# Blue_Cobra.net
KiCad netlist of a schematic drawn in EAGLE
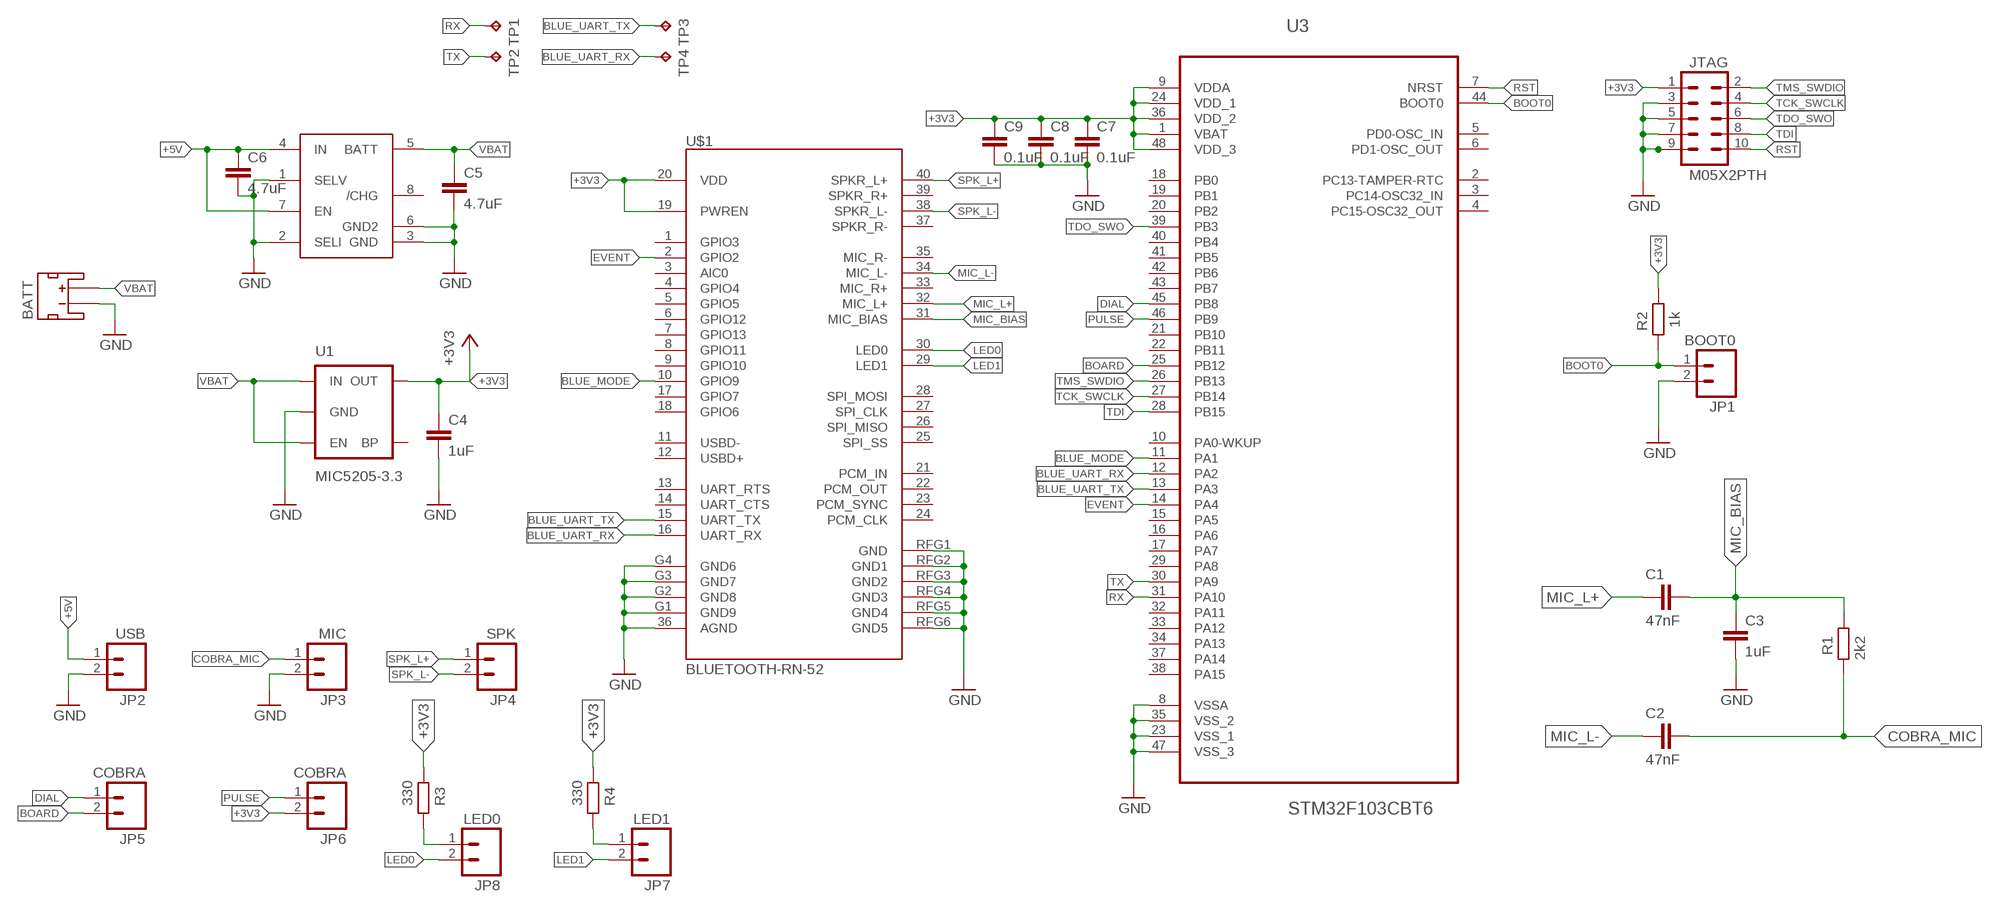
[diagram p0: schematic, sheet 1]

(export (version "E")
  (design (tool "Eeschema 10.0.6"))
  (components
    (comp (ref "BATT")
      (value "JST_2MM_MALE")
      (footprint "eagle-import:JST-2-SMD")
      (libsource (lib "eagle-import") (part "JST_2MM_MALE"))
    )
    (comp (ref "C1")
      (value "47nF")
      (footprint "eagle-import:C0805")
      (libsource (lib "eagle-import") (part "C-EUC0805"))
    )
    (comp (ref "C2")
      (value "47nF")
      (footprint "eagle-import:C0805")
      (libsource (lib "eagle-import") (part "C-EUC0805"))
    )
    (comp (ref "C3")
      (value "1uF")
      (footprint "eagle-import:C0805")
      (libsource (lib "eagle-import") (part "C-EUC0805"))
    )
    (comp (ref "C4")
      (value "1uF")
      (footprint "eagle-import:C0805")
      (libsource (lib "eagle-import") (part "C-EUC0805"))
    )
    (comp (ref "C5")
      (value "4.7uF")
      (footprint "eagle-import:C0805")
      (libsource (lib "eagle-import") (part "C-EUC0805"))
    )
    (comp (ref "C6")
      (value "4.7uF")
      (footprint "eagle-import:C0805")
      (libsource (lib "eagle-import") (part "C-EUC0805"))
    )
    (comp (ref "C7")
      (value "0.1uF")
      (footprint "eagle-import:C0805")
      (libsource (lib "eagle-import") (part "C-EUC0805"))
    )
    (comp (ref "C8")
      (value "0.1uF")
      (footprint "eagle-import:C0805")
      (libsource (lib "eagle-import") (part "C-EUC0805"))
    )
    (comp (ref "C9")
      (value "0.1uF")
      (footprint "eagle-import:C0805")
      (libsource (lib "eagle-import") (part "C-EUC0805"))
    )
    (comp (ref "JP1")
      (value "BOOT0")
      (footprint "eagle-import:1X02_NO_SILK")
      (libsource (lib "eagle-import") (part "M021X02_NO_SILK"))
    )
    (comp (ref "JP2")
      (value "USB")
      (footprint "eagle-import:1X02_NO_SILK")
      (libsource (lib "eagle-import") (part "M021X02_NO_SILK"))
    )
    (comp (ref "JP3")
      (value "MIC")
      (footprint "eagle-import:1X02_NO_SILK")
      (libsource (lib "eagle-import") (part "M021X02_NO_SILK"))
    )
    (comp (ref "JP4")
      (value "SPK")
      (footprint "eagle-import:1X02_NO_SILK")
      (libsource (lib "eagle-import") (part "M021X02_NO_SILK"))
    )
    (comp (ref "JP5")
      (value "COBRA")
      (footprint "eagle-import:1X02_NO_SILK")
      (libsource (lib "eagle-import") (part "M021X02_NO_SILK"))
    )
    (comp (ref "JP6")
      (value "COBRA")
      (footprint "eagle-import:1X02_NO_SILK")
      (libsource (lib "eagle-import") (part "M021X02_NO_SILK"))
    )
    (comp (ref "JP7")
      (value "LED1")
      (footprint "eagle-import:1X02_NO_SILK")
      (libsource (lib "eagle-import") (part "M021X02_NO_SILK"))
    )
    (comp (ref "JP8")
      (value "LED0")
      (footprint "eagle-import:1X02_NO_SILK")
      (libsource (lib "eagle-import") (part "M021X02_NO_SILK"))
    )
    (comp (ref "JTAG")
      (value "M05X2PTH")
      (footprint "eagle-import:AVR_ICSP")
      (libsource (lib "eagle-import") (part "M05X2PTH"))
    )
    (comp (ref "R1")
      (value "2k2")
      (footprint "eagle-import:R0805")
      (libsource (lib "eagle-import") (part "R-EU_R0805"))
    )
    (comp (ref "R2")
      (value "1k")
      (footprint "eagle-import:R0805")
      (libsource (lib "eagle-import") (part "R-EU_R0805"))
    )
    (comp (ref "R3")
      (value "330")
      (footprint "eagle-import:R0805")
      (libsource (lib "eagle-import") (part "R-EU_R0805"))
    )
    (comp (ref "R4")
      (value "330")
      (footprint "eagle-import:R0805")
      (libsource (lib "eagle-import") (part "R-EU_R0805"))
    )
    (comp (ref "TP1")
      (value "TPTP10SQ")
      (footprint "eagle-import:TP10SQ")
      (libsource (lib "eagle-import") (part "TPTP10SQ"))
    )
    (comp (ref "TP2")
      (value "TPTP10SQ")
      (footprint "eagle-import:TP10SQ")
      (libsource (lib "eagle-import") (part "TPTP10SQ"))
    )
    (comp (ref "TP3")
      (value "TPTP10SQ")
      (footprint "eagle-import:TP10SQ")
      (libsource (lib "eagle-import") (part "TPTP10SQ"))
    )
    (comp (ref "TP4")
      (value "TPTP10SQ")
      (footprint "eagle-import:TP10SQ")
      (libsource (lib "eagle-import") (part "TPTP10SQ"))
    )
    (comp (ref "U$1")
      (value "BLUETOOTH-RN-52")
      (footprint "eagle-import:RN-52")
      (libsource (lib "eagle-import") (part "BLUETOOTH-RN-52"))
    )
    (comp (ref "U1")
      (value "MIC5205-3.3")
      (footprint "eagle-import:SOT23-5")
      (libsource (lib "eagle-import") (part "MIC52053.3V"))
    )
    (comp (ref "U2")
      (value "MAX1811SO8")
      (footprint "eagle-import:SO08")
      (libsource (lib "eagle-import") (part "MAX1811SO8"))
    )
    (comp (ref "U3")
      (value "STM32F103CBT6")
      (footprint "eagle-import:QFP50P900X900X160-48N")
      (libsource (lib "eagle-import") (part "STM32F103CBT6"))
    )
  )
  (nets
    (net (code "1") (name "+3V3") (class "Default")
      (node (ref "C4") (pin "1") (pinfunction "1_1") (pintype "passive"))
      (node (ref "C7") (pin "1") (pinfunction "1_1") (pintype "passive"))
      (node (ref "C8") (pin "1") (pinfunction "1_1") (pintype "passive"))
      (node (ref "C9") (pin "1") (pinfunction "1_1") (pintype "passive"))
      (node (ref "JP6") (pin "2") (pinfunction "2_2") (pintype "passive"))
      (node (ref "JTAG") (pin "1") (pinfunction "1_1") (pintype "passive"))
      (node (ref "R2") (pin "2") (pinfunction "2_2") (pintype "passive"))
      (node (ref "R3") (pin "1") (pinfunction "1_1") (pintype "passive"))
      (node (ref "R4") (pin "1") (pinfunction "1_1") (pintype "passive"))
      (node (ref "U$1") (pin "19") (pinfunction "PWREN_19") (pintype "bidirectional"))
      (node (ref "U$1") (pin "20") (pinfunction "VDD_20") (pintype "bidirectional"))
      (node (ref "U1") (pin "5") (pinfunction "OUT_5") (pintype "passive"))
      (node (ref "U3") (pin "1") (pinfunction "VBAT_1") (pintype "input"))
      (node (ref "U3") (pin "24") (pinfunction "VDD_1_24") (pintype "bidirectional"))
      (node (ref "U3") (pin "36") (pinfunction "VDD_2_36") (pintype "power_in"))
      (node (ref "U3") (pin "48") (pinfunction "VDD_3_48") (pintype "power_in"))
      (node (ref "U3") (pin "9") (pinfunction "VDDA_9") (pintype "power_in"))
    )
    (net (code "2") (name "+5V") (class "Default")
      (node (ref "C6") (pin "1") (pinfunction "1_1") (pintype "passive"))
      (node (ref "JP2") (pin "1") (pinfunction "1_1") (pintype "passive"))
      (node (ref "U2") (pin "4") (pinfunction "IN_4") (pintype "bidirectional"))
      (node (ref "U2") (pin "7") (pinfunction "EN_7") (pintype "bidirectional"))
    )
    (net (code "3") (name "/PA11") (class "Default")
      (node (ref "U3") (pin "32") (pinfunction "PA11_32") (pintype "power_in"))
    )
    (net (code "4") (name "BLUE_MODE") (class "Default")
      (node (ref "U$1") (pin "10") (pinfunction "GPIO9_10") (pintype "bidirectional"))
      (node (ref "U3") (pin "11") (pinfunction "PA1_11") (pintype "bidirectional"))
    )
    (net (code "5") (name "BLUE_UART_RX") (class "Default")
      (node (ref "TP4") (pin "TP") (pinfunction "TP_TP") (pintype "input"))
      (node (ref "U$1") (pin "16") (pinfunction "UART_RX_16") (pintype "bidirectional"))
      (node (ref "U3") (pin "12") (pinfunction "PA2_12") (pintype "bidirectional"))
    )
    (net (code "6") (name "BLUE_UART_TX") (class "Default")
      (node (ref "TP3") (pin "TP") (pinfunction "TP_TP") (pintype "input"))
      (node (ref "U$1") (pin "15") (pinfunction "UART_TX_15") (pintype "bidirectional"))
      (node (ref "U3") (pin "13") (pinfunction "PA3_13") (pintype "bidirectional"))
    )
    (net (code "7") (name "BOARD") (class "Default")
      (node (ref "JP5") (pin "2") (pinfunction "2_2") (pintype "passive"))
      (node (ref "U3") (pin "25") (pinfunction "PB12_25") (pintype "bidirectional"))
    )
    (net (code "8") (name "BOOT0") (class "Default")
      (node (ref "JP1") (pin "1") (pinfunction "1_1") (pintype "passive"))
      (node (ref "R2") (pin "1") (pinfunction "1_1") (pintype "passive"))
      (node (ref "U3") (pin "44") (pinfunction "BOOT0_44") (pintype "bidirectional"))
    )
    (net (code "9") (name "COBRA_MIC") (class "Default")
      (node (ref "C2") (pin "2") (pinfunction "2_2") (pintype "passive"))
      (node (ref "JP3") (pin "1") (pinfunction "1_1") (pintype "passive"))
      (node (ref "R1") (pin "1") (pinfunction "1_1") (pintype "passive"))
    )
    (net (code "10") (name "DIAL") (class "Default")
      (node (ref "JP5") (pin "1") (pinfunction "1_1") (pintype "passive"))
      (node (ref "U3") (pin "45") (pinfunction "PB8_45") (pintype "bidirectional"))
    )
    (net (code "11") (name "EVENT") (class "Default")
      (node (ref "U$1") (pin "2") (pinfunction "GPIO2_2") (pintype "bidirectional"))
      (node (ref "U3") (pin "14") (pinfunction "PA4_14") (pintype "bidirectional"))
    )
    (net (code "12") (name "GND") (class "Default")
      (node (ref "BATT") (pin "1") (pinfunction "-_1") (pintype "bidirectional"))
      (node (ref "C3") (pin "2") (pinfunction "2_2") (pintype "passive"))
      (node (ref "C4") (pin "2") (pinfunction "2_2") (pintype "passive"))
      (node (ref "C5") (pin "2") (pinfunction "2_2") (pintype "passive"))
      (node (ref "C6") (pin "2") (pinfunction "2_2") (pintype "passive"))
      (node (ref "C7") (pin "2") (pinfunction "2_2") (pintype "passive"))
      (node (ref "C8") (pin "2") (pinfunction "2_2") (pintype "passive"))
      (node (ref "C9") (pin "2") (pinfunction "2_2") (pintype "passive"))
      (node (ref "JP1") (pin "2") (pinfunction "2_2") (pintype "passive"))
      (node (ref "JP2") (pin "2") (pinfunction "2_2") (pintype "passive"))
      (node (ref "JP3") (pin "2") (pinfunction "2_2") (pintype "passive"))
      (node (ref "JTAG") (pin "3") (pinfunction "3_3") (pintype "passive"))
      (node (ref "JTAG") (pin "5") (pinfunction "5_5") (pintype "passive"))
      (node (ref "JTAG") (pin "7") (pinfunction "7_7") (pintype "passive"))
      (node (ref "JTAG") (pin "9") (pinfunction "9_9") (pintype "passive"))
      (node (ref "U$1") (pin "36") (pinfunction "AGND_36") (pintype "bidirectional"))
      (node (ref "U$1") (pin "G1") (pinfunction "GND9_G1") (pintype "bidirectional"))
      (node (ref "U$1") (pin "G2") (pinfunction "GND8_G2") (pintype "bidirectional"))
      (node (ref "U$1") (pin "G3") (pinfunction "GND7_G3") (pintype "bidirectional"))
      (node (ref "U$1") (pin "G4") (pinfunction "GND6_G4") (pintype "bidirectional"))
      (node (ref "U$1") (pin "RFG1") (pinfunction "GND_RFG1") (pintype "bidirectional"))
      (node (ref "U$1") (pin "RFG2") (pinfunction "GND1_RFG2") (pintype "bidirectional"))
      (node (ref "U$1") (pin "RFG3") (pinfunction "GND2_RFG3") (pintype "bidirectional"))
      (node (ref "U$1") (pin "RFG4") (pinfunction "GND3_RFG4") (pintype "bidirectional"))
      (node (ref "U$1") (pin "RFG5") (pinfunction "GND4_RFG5") (pintype "bidirectional"))
      (node (ref "U$1") (pin "RFG6") (pinfunction "GND5_RFG6") (pintype "bidirectional"))
      (node (ref "U1") (pin "2") (pinfunction "GND_2") (pintype "input"))
      (node (ref "U2") (pin "1") (pinfunction "SELV_1") (pintype "bidirectional"))
      (node (ref "U2") (pin "2") (pinfunction "SELI_2") (pintype "bidirectional"))
      (node (ref "U2") (pin "3") (pinfunction "GND_3") (pintype "bidirectional"))
      (node (ref "U2") (pin "6") (pinfunction "GND2_6") (pintype "bidirectional"))
      (node (ref "U3") (pin "23") (pinfunction "VSS_1_23") (pintype "bidirectional"))
      (node (ref "U3") (pin "35") (pinfunction "VSS_2_35") (pintype "passive"))
      (node (ref "U3") (pin "47") (pinfunction "VSS_3_47") (pintype "passive"))
      (node (ref "U3") (pin "8") (pinfunction "VSSA_8") (pintype "passive"))
    )
    (net (code "13") (name "LED0") (class "Default")
      (node (ref "JP8") (pin "2") (pinfunction "2_2") (pintype "passive"))
      (node (ref "U$1") (pin "30") (pinfunction "LED0_30") (pintype "bidirectional"))
    )
    (net (code "14") (name "LED1") (class "Default")
      (node (ref "JP7") (pin "2") (pinfunction "2_2") (pintype "passive"))
      (node (ref "U$1") (pin "29") (pinfunction "LED1_29") (pintype "bidirectional"))
    )
    (net (code "15") (name "MIC_BIAS") (class "Default")
      (node (ref "C1") (pin "2") (pinfunction "2_2") (pintype "passive"))
      (node (ref "C3") (pin "1") (pinfunction "1_1") (pintype "passive"))
      (node (ref "R1") (pin "2") (pinfunction "2_2") (pintype "passive"))
      (node (ref "U$1") (pin "31") (pinfunction "MIC_BIAS_31") (pintype "bidirectional"))
    )
    (net (code "16") (name "MIC_L+") (class "Default")
      (node (ref "C1") (pin "1") (pinfunction "1_1") (pintype "passive"))
      (node (ref "U$1") (pin "32") (pinfunction "MIC_L+_32") (pintype "bidirectional"))
    )
    (net (code "17") (name "MIC_L-") (class "Default")
      (node (ref "C2") (pin "1") (pinfunction "1_1") (pintype "passive"))
      (node (ref "U$1") (pin "34") (pinfunction "MIC_L-_34") (pintype "bidirectional"))
    )
    (net (code "18") (name "Net-(JP7-Pad1)") (class "Default")
      (node (ref "JP7") (pin "1") (pinfunction "1_1") (pintype "passive"))
      (node (ref "R4") (pin "2") (pinfunction "2_2") (pintype "passive"))
    )
    (net (code "19") (name "Net-(JP8-Pad1)") (class "Default")
      (node (ref "JP8") (pin "1") (pinfunction "1_1") (pintype "passive"))
      (node (ref "R3") (pin "2") (pinfunction "2_2") (pintype "passive"))
    )
    (net (code "20") (name "PULSE") (class "Default")
      (node (ref "JP6") (pin "1") (pinfunction "1_1") (pintype "passive"))
      (node (ref "U3") (pin "46") (pinfunction "PB9_46") (pintype "bidirectional"))
    )
    (net (code "21") (name "RST") (class "Default")
      (node (ref "JTAG") (pin "10") (pinfunction "10_10") (pintype "passive"))
      (node (ref "U3") (pin "7") (pinfunction "NRST_7") (pintype "bidirectional"))
    )
    (net (code "22") (name "RX") (class "Default")
      (node (ref "TP1") (pin "TP") (pinfunction "TP_TP") (pintype "input"))
      (node (ref "U3") (pin "31") (pinfunction "PA10_31") (pintype "bidirectional"))
    )
    (net (code "23") (name "SPK_L+") (class "Default")
      (node (ref "JP4") (pin "1") (pinfunction "1_1") (pintype "passive"))
      (node (ref "U$1") (pin "40") (pinfunction "SPKR_L+_40") (pintype "bidirectional"))
    )
    (net (code "24") (name "SPK_L-") (class "Default")
      (node (ref "JP4") (pin "2") (pinfunction "2_2") (pintype "passive"))
      (node (ref "U$1") (pin "38") (pinfunction "SPKR_L-_38") (pintype "bidirectional"))
    )
    (net (code "25") (name "TCK_SWCLK") (class "Default")
      (node (ref "JTAG") (pin "4") (pinfunction "4_4") (pintype "passive"))
      (node (ref "U3") (pin "27") (pinfunction "PB14_27") (pintype "bidirectional"))
    )
    (net (code "26") (name "TDI") (class "Default")
      (node (ref "JTAG") (pin "8") (pinfunction "8_8") (pintype "passive"))
      (node (ref "U3") (pin "28") (pinfunction "PB15_28") (pintype "bidirectional"))
    )
    (net (code "27") (name "TDO_SWO") (class "Default")
      (node (ref "JTAG") (pin "6") (pinfunction "6_6") (pintype "passive"))
      (node (ref "U3") (pin "39") (pinfunction "PB3_39") (pintype "bidirectional"))
    )
    (net (code "28") (name "TMS_SWDIO") (class "Default")
      (node (ref "JTAG") (pin "2") (pinfunction "2_2") (pintype "passive"))
      (node (ref "U3") (pin "26") (pinfunction "PB13_26") (pintype "bidirectional"))
    )
    (net (code "29") (name "TX") (class "Default")
      (node (ref "TP2") (pin "TP") (pinfunction "TP_TP") (pintype "input"))
      (node (ref "U3") (pin "30") (pinfunction "PA9_30") (pintype "bidirectional"))
    )
    (net (code "30") (name "VBAT") (class "Default")
      (node (ref "BATT") (pin "2") (pinfunction "+_2") (pintype "bidirectional"))
      (node (ref "C5") (pin "1") (pinfunction "1_1") (pintype "passive"))
      (node (ref "U1") (pin "1") (pinfunction "IN_1") (pintype "input"))
      (node (ref "U1") (pin "3") (pinfunction "EN_3") (pintype "input"))
      (node (ref "U2") (pin "5") (pinfunction "BATT_5") (pintype "bidirectional"))
    )
    (net (code "31") (name "unconnected-(BATT-PAD1-PadNC1)") (class "Default")
      (node (ref "BATT") (pin "NC1") (pinfunction "PAD1_NC1") (pintype "bidirectional"))
    )
    (net (code "32") (name "unconnected-(BATT-PAD2-PadNC2)") (class "Default")
      (node (ref "BATT") (pin "NC2") (pinfunction "PAD2_NC2") (pintype "bidirectional"))
    )
    (net (code "33") (name "unconnected-(U$1-AIC0-Pad3)") (class "Default")
      (node (ref "U$1") (pin "3") (pinfunction "AIC0_3") (pintype "bidirectional"))
    )
    (net (code "34") (name "unconnected-(U$1-GPIO3-Pad1)") (class "Default")
      (node (ref "U$1") (pin "1") (pinfunction "GPIO3_1") (pintype "bidirectional"))
    )
    (net (code "35") (name "unconnected-(U$1-GPIO4-Pad4)") (class "Default")
      (node (ref "U$1") (pin "4") (pinfunction "GPIO4_4") (pintype "bidirectional"))
    )
    (net (code "36") (name "unconnected-(U$1-GPIO5-Pad5)") (class "Default")
      (node (ref "U$1") (pin "5") (pinfunction "GPIO5_5") (pintype "bidirectional"))
    )
    (net (code "37") (name "unconnected-(U$1-GPIO6-Pad18)") (class "Default")
      (node (ref "U$1") (pin "18") (pinfunction "GPIO6_18") (pintype "bidirectional"))
    )
    (net (code "38") (name "unconnected-(U$1-GPIO7-Pad17)") (class "Default")
      (node (ref "U$1") (pin "17") (pinfunction "GPIO7_17") (pintype "bidirectional"))
    )
    (net (code "39") (name "unconnected-(U$1-GPIO10-Pad9)") (class "Default")
      (node (ref "U$1") (pin "9") (pinfunction "GPIO10_9") (pintype "bidirectional"))
    )
    (net (code "40") (name "unconnected-(U$1-GPIO11-Pad8)") (class "Default")
      (node (ref "U$1") (pin "8") (pinfunction "GPIO11_8") (pintype "bidirectional"))
    )
    (net (code "41") (name "unconnected-(U$1-GPIO12-Pad6)") (class "Default")
      (node (ref "U$1") (pin "6") (pinfunction "GPIO12_6") (pintype "bidirectional"))
    )
    (net (code "42") (name "unconnected-(U$1-GPIO13-Pad7)") (class "Default")
      (node (ref "U$1") (pin "7") (pinfunction "GPIO13_7") (pintype "bidirectional"))
    )
    (net (code "43") (name "unconnected-(U$1-MIC_R+-Pad33)") (class "Default")
      (node (ref "U$1") (pin "33") (pinfunction "MIC_R+_33") (pintype "bidirectional"))
    )
    (net (code "44") (name "unconnected-(U$1-MIC_R--Pad35)") (class "Default")
      (node (ref "U$1") (pin "35") (pinfunction "MIC_R-_35") (pintype "bidirectional"))
    )
    (net (code "45") (name "unconnected-(U$1-PCM_CLK-Pad24)") (class "Default")
      (node (ref "U$1") (pin "24") (pinfunction "PCM_CLK_24") (pintype "bidirectional"))
    )
    (net (code "46") (name "unconnected-(U$1-PCM_IN-Pad21)") (class "Default")
      (node (ref "U$1") (pin "21") (pinfunction "PCM_IN_21") (pintype "bidirectional"))
    )
    (net (code "47") (name "unconnected-(U$1-PCM_OUT-Pad22)") (class "Default")
      (node (ref "U$1") (pin "22") (pinfunction "PCM_OUT_22") (pintype "bidirectional"))
    )
    (net (code "48") (name "unconnected-(U$1-PCM_SYNC-Pad23)") (class "Default")
      (node (ref "U$1") (pin "23") (pinfunction "PCM_SYNC_23") (pintype "bidirectional"))
    )
    (net (code "49") (name "unconnected-(U$1-SPI_CLK-Pad27)") (class "Default")
      (node (ref "U$1") (pin "27") (pinfunction "SPI_CLK_27") (pintype "bidirectional"))
    )
    (net (code "50") (name "unconnected-(U$1-SPI_MISO-Pad26)") (class "Default")
      (node (ref "U$1") (pin "26") (pinfunction "SPI_MISO_26") (pintype "bidirectional"))
    )
    (net (code "51") (name "unconnected-(U$1-SPI_MOSI-Pad28)") (class "Default")
      (node (ref "U$1") (pin "28") (pinfunction "SPI_MOSI_28") (pintype "bidirectional"))
    )
    (net (code "52") (name "unconnected-(U$1-SPI_SS-Pad25)") (class "Default")
      (node (ref "U$1") (pin "25") (pinfunction "SPI_SS_25") (pintype "bidirectional"))
    )
    (net (code "53") (name "unconnected-(U$1-SPKR_R+-Pad39)") (class "Default")
      (node (ref "U$1") (pin "39") (pinfunction "SPKR_R+_39") (pintype "bidirectional"))
    )
    (net (code "54") (name "unconnected-(U$1-SPKR_R--Pad37)") (class "Default")
      (node (ref "U$1") (pin "37") (pinfunction "SPKR_R-_37") (pintype "bidirectional"))
    )
    (net (code "55") (name "unconnected-(U$1-UART_CTS-Pad14)") (class "Default")
      (node (ref "U$1") (pin "14") (pinfunction "UART_CTS_14") (pintype "bidirectional"))
    )
    (net (code "56") (name "unconnected-(U$1-UART_RTS-Pad13)") (class "Default")
      (node (ref "U$1") (pin "13") (pinfunction "UART_RTS_13") (pintype "bidirectional"))
    )
    (net (code "57") (name "unconnected-(U$1-USBD+-Pad12)") (class "Default")
      (node (ref "U$1") (pin "12") (pinfunction "USBD+_12") (pintype "bidirectional"))
    )
    (net (code "58") (name "unconnected-(U$1-USBD--Pad11)") (class "Default")
      (node (ref "U$1") (pin "11") (pinfunction "USBD-_11") (pintype "bidirectional"))
    )
    (net (code "59") (name "unconnected-(U1-BP-Pad4)") (class "Default")
      (node (ref "U1") (pin "4") (pinfunction "BP_4") (pintype "input"))
    )
    (net (code "60") (name "unconnected-(U2-{slash}CHG-Pad8)") (class "Default")
      (node (ref "U2") (pin "8") (pinfunction "/CHG_8") (pintype "bidirectional"))
    )
    (net (code "61") (name "unconnected-(U3-PA0-WKUP-Pad10)") (class "Default")
      (node (ref "U3") (pin "10") (pinfunction "PA0-WKUP_10") (pintype "bidirectional"))
    )
    (net (code "62") (name "unconnected-(U3-PA5-Pad15)") (class "Default")
      (node (ref "U3") (pin "15") (pinfunction "PA5_15") (pintype "bidirectional"))
    )
    (net (code "63") (name "unconnected-(U3-PA6-Pad16)") (class "Default")
      (node (ref "U3") (pin "16") (pinfunction "PA6_16") (pintype "bidirectional"))
    )
    (net (code "64") (name "unconnected-(U3-PA7-Pad17)") (class "Default")
      (node (ref "U3") (pin "17") (pinfunction "PA7_17") (pintype "bidirectional"))
    )
    (net (code "65") (name "unconnected-(U3-PA8-Pad29)") (class "Default")
      (node (ref "U3") (pin "29") (pinfunction "PA8_29") (pintype "bidirectional"))
    )
    (net (code "66") (name "unconnected-(U3-PA12-Pad33)") (class "Default")
      (node (ref "U3") (pin "33") (pinfunction "PA12_33") (pintype "bidirectional"))
    )
    (net (code "67") (name "unconnected-(U3-PA13-Pad34)") (class "Default")
      (node (ref "U3") (pin "34") (pinfunction "PA13_34") (pintype "bidirectional"))
    )
    (net (code "68") (name "unconnected-(U3-PA14-Pad37)") (class "Default")
      (node (ref "U3") (pin "37") (pinfunction "PA14_37") (pintype "bidirectional"))
    )
    (net (code "69") (name "unconnected-(U3-PA15-Pad38)") (class "Default")
      (node (ref "U3") (pin "38") (pinfunction "PA15_38") (pintype "bidirectional"))
    )
    (net (code "70") (name "unconnected-(U3-PB0-Pad18)") (class "Default")
      (node (ref "U3") (pin "18") (pinfunction "PB0_18") (pintype "bidirectional"))
    )
    (net (code "71") (name "unconnected-(U3-PB1-Pad19)") (class "Default")
      (node (ref "U3") (pin "19") (pinfunction "PB1_19") (pintype "bidirectional"))
    )
    (net (code "72") (name "unconnected-(U3-PB2-Pad20)") (class "Default")
      (node (ref "U3") (pin "20") (pinfunction "PB2_20") (pintype "bidirectional"))
    )
    (net (code "73") (name "unconnected-(U3-PB4-Pad40)") (class "Default")
      (node (ref "U3") (pin "40") (pinfunction "PB4_40") (pintype "bidirectional"))
    )
    (net (code "74") (name "unconnected-(U3-PB5-Pad41)") (class "Default")
      (node (ref "U3") (pin "41") (pinfunction "PB5_41") (pintype "bidirectional"))
    )
    (net (code "75") (name "unconnected-(U3-PB6-Pad42)") (class "Default")
      (node (ref "U3") (pin "42") (pinfunction "PB6_42") (pintype "bidirectional"))
    )
    (net (code "76") (name "unconnected-(U3-PB7-Pad43)") (class "Default")
      (node (ref "U3") (pin "43") (pinfunction "PB7_43") (pintype "bidirectional"))
    )
    (net (code "77") (name "unconnected-(U3-PB10-Pad21)") (class "Default")
      (node (ref "U3") (pin "21") (pinfunction "PB10_21") (pintype "bidirectional"))
    )
    (net (code "78") (name "unconnected-(U3-PB11-Pad22)") (class "Default")
      (node (ref "U3") (pin "22") (pinfunction "PB11_22") (pintype "bidirectional"))
    )
    (net (code "79") (name "unconnected-(U3-PC13-TAMPER-RTC-Pad2)") (class "Default")
      (node (ref "U3") (pin "2") (pinfunction "PC13-TAMPER-RTC_2") (pintype "bidirectional"))
    )
    (net (code "80") (name "unconnected-(U3-PC14-OSC32_IN-Pad3)") (class "Default")
      (node (ref "U3") (pin "3") (pinfunction "PC14-OSC32_IN_3") (pintype "bidirectional"))
    )
    (net (code "81") (name "unconnected-(U3-PC15-OSC32_OUT-Pad4)") (class "Default")
      (node (ref "U3") (pin "4") (pinfunction "PC15-OSC32_OUT_4") (pintype "bidirectional"))
    )
    (net (code "82") (name "unconnected-(U3-PD0-OSC_IN-Pad5)") (class "Default")
      (node (ref "U3") (pin "5") (pinfunction "PD0-OSC_IN_5") (pintype "bidirectional"))
    )
    (net (code "83") (name "unconnected-(U3-PD1-OSC_OUT-Pad6)") (class "Default")
      (node (ref "U3") (pin "6") (pinfunction "PD1-OSC_OUT_6") (pintype "bidirectional"))
    )
  )
)
